# DotShine.net
KiCad netlist of a schematic drawn in EAGLE
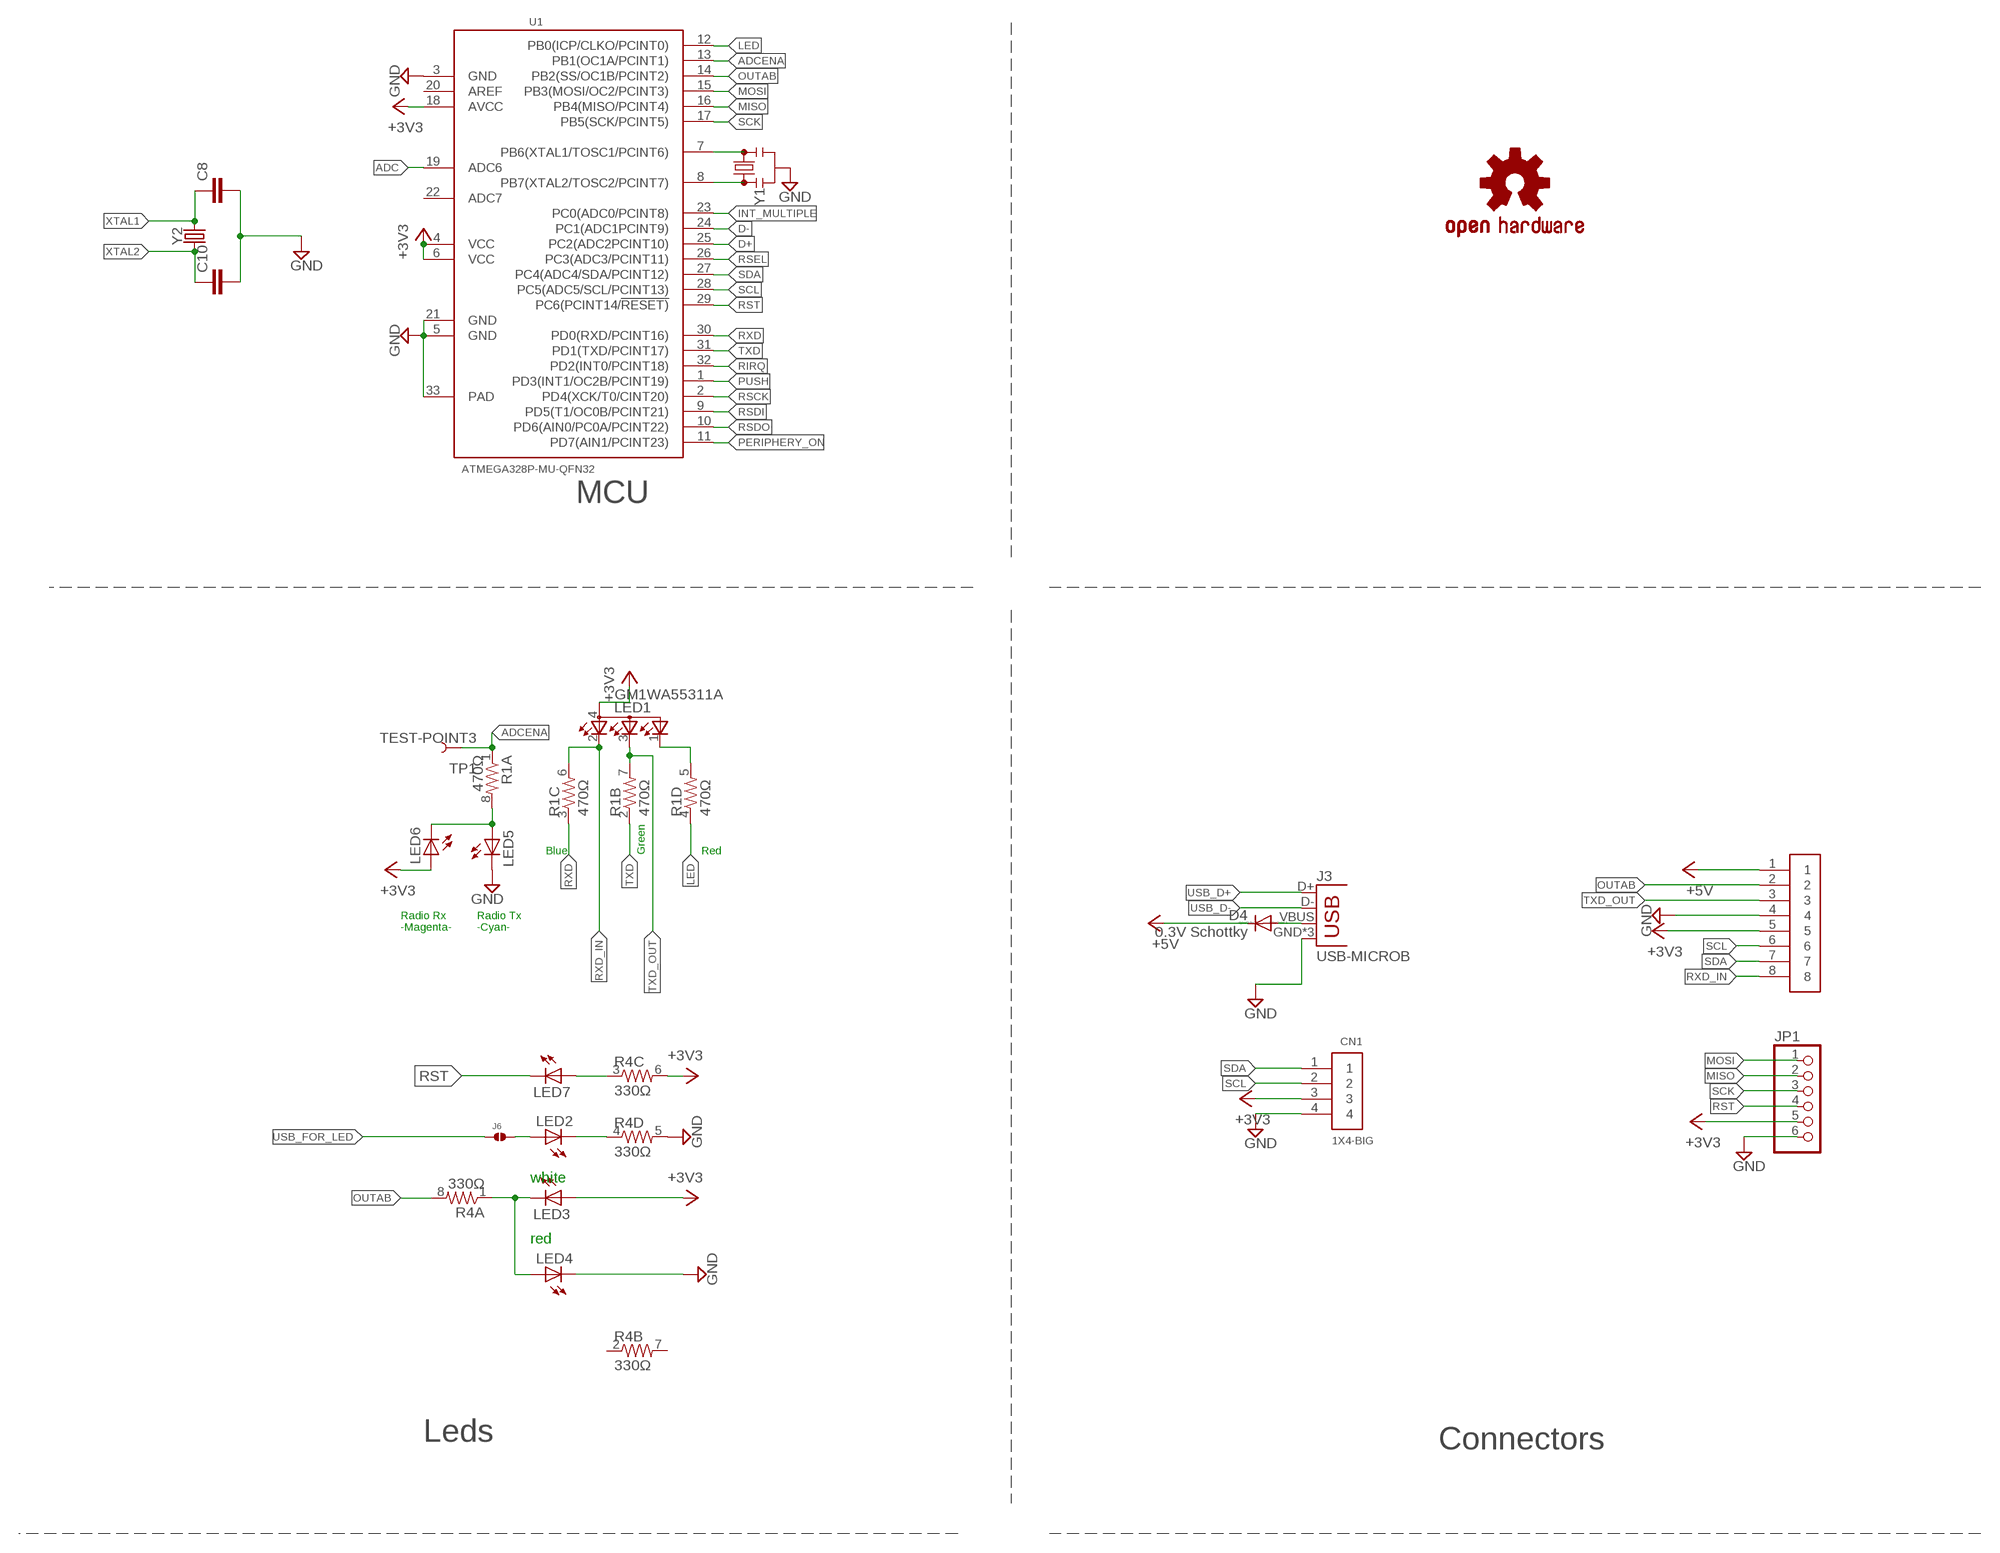
[diagram p0: schematic, sheet 1, part 1 of 3]
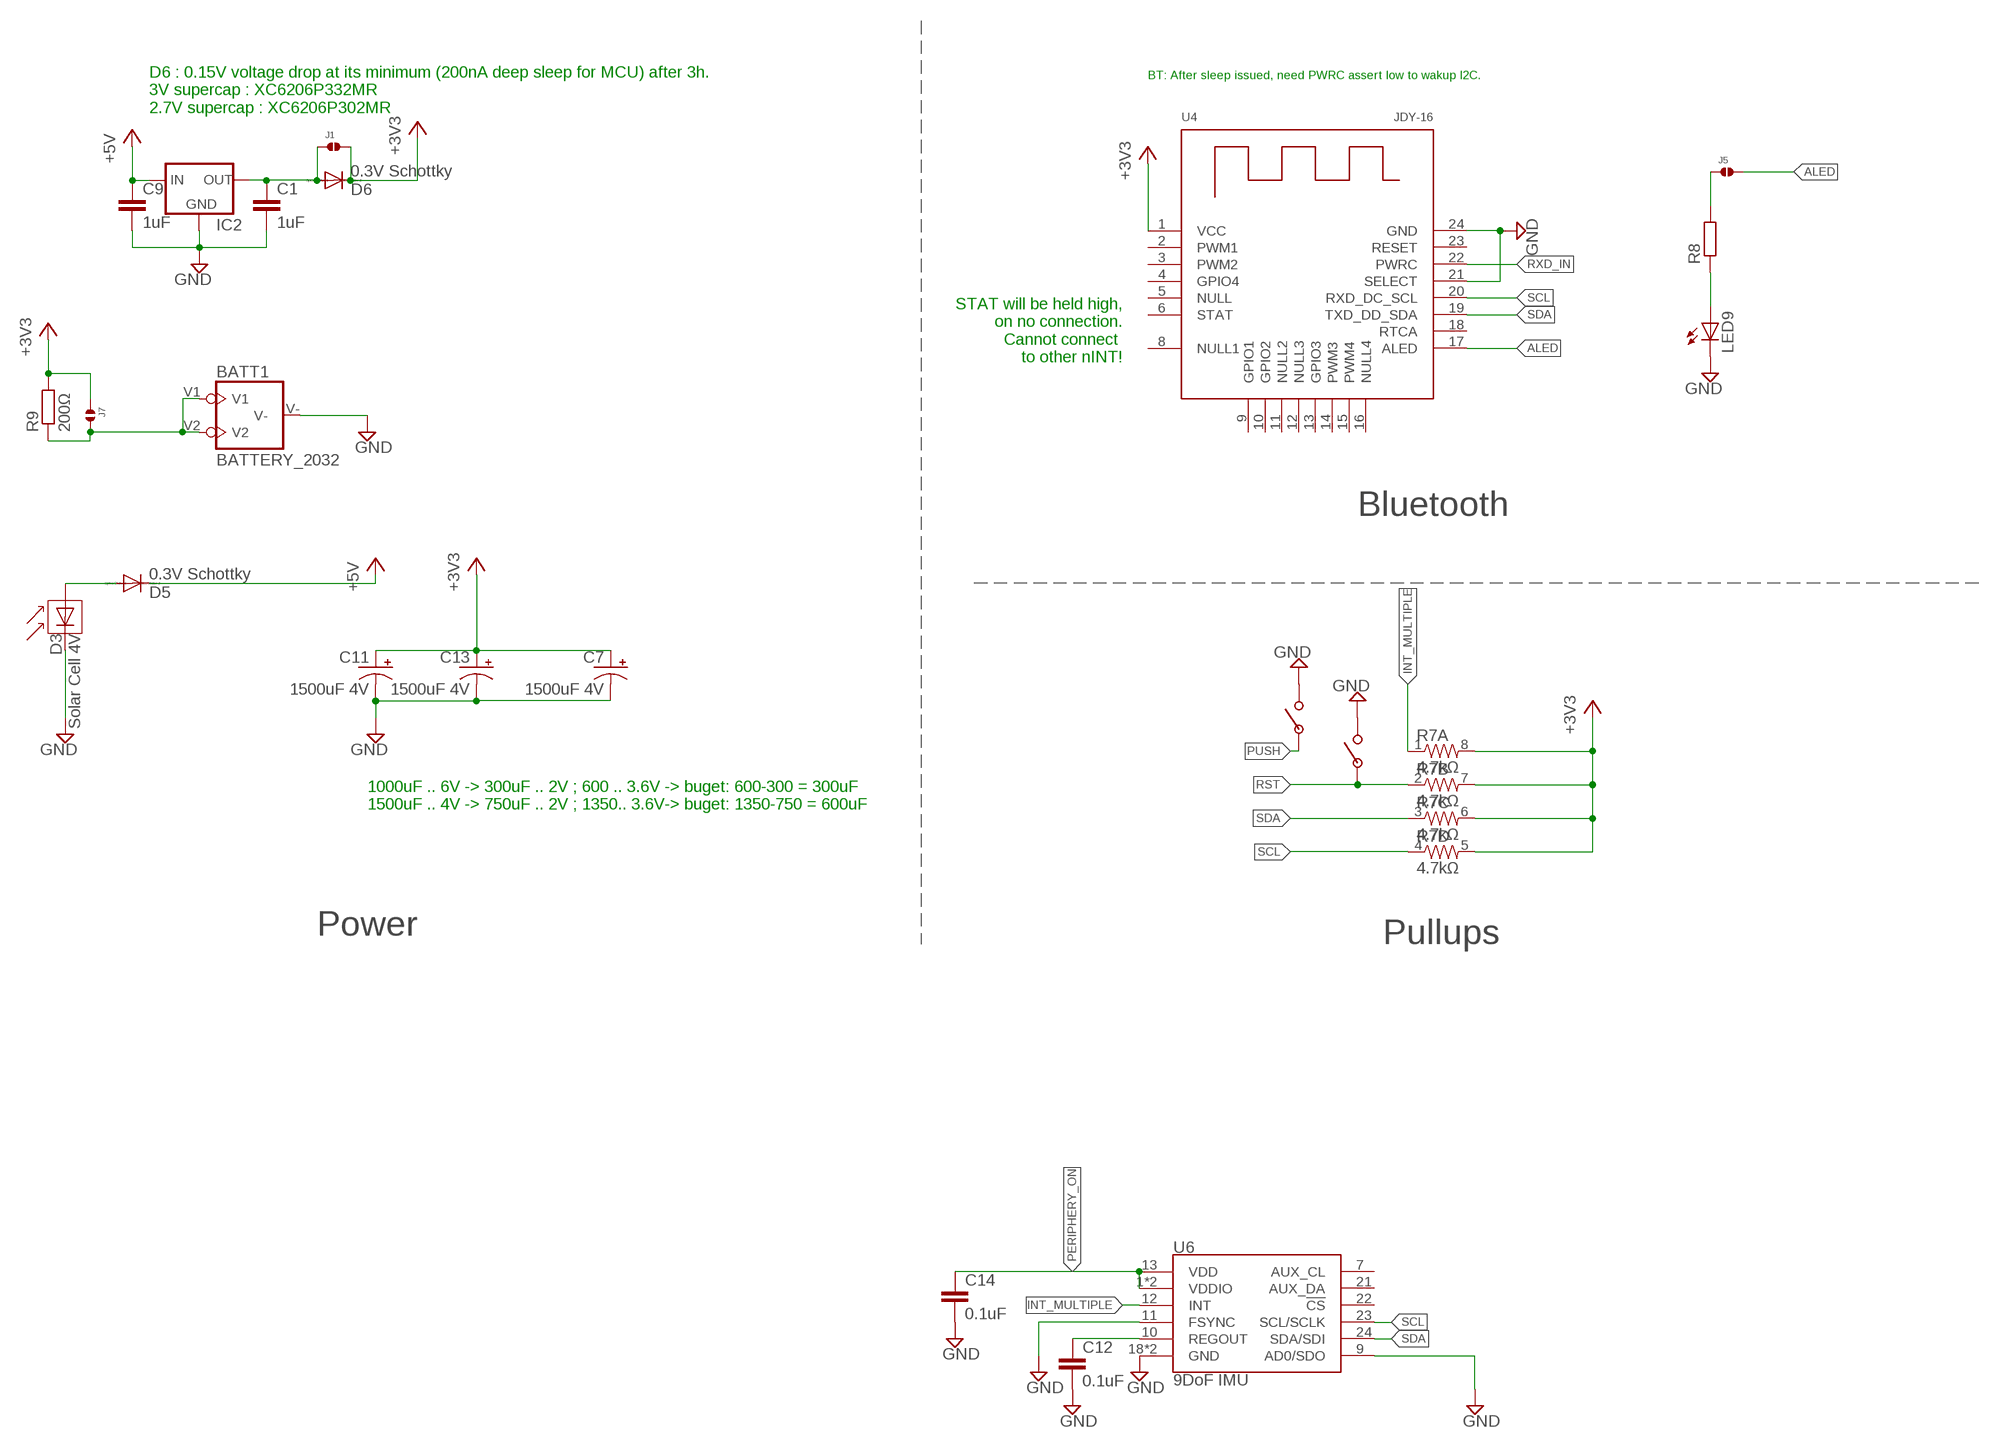
[diagram p1: schematic, sheet 1, part 2 of 3]
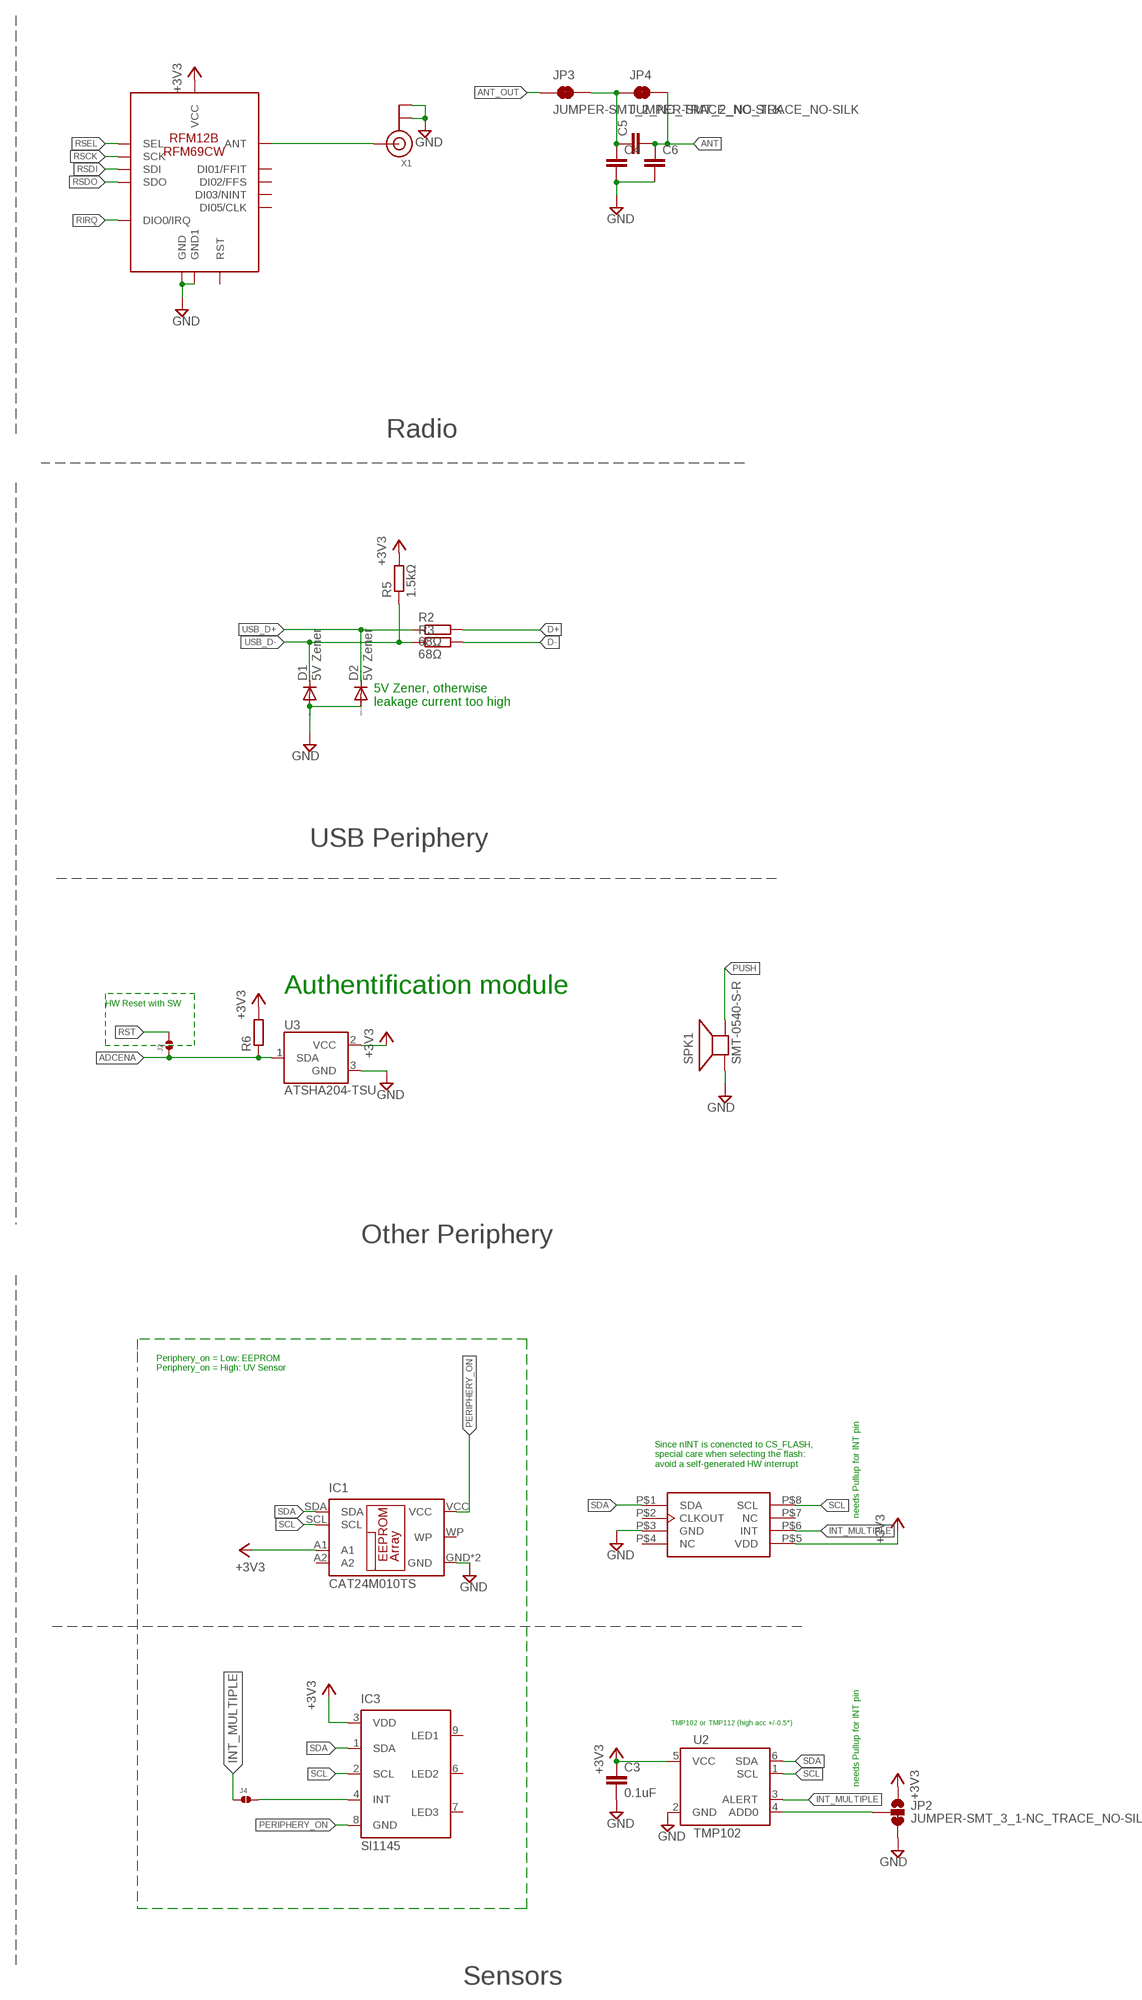
[diagram p2: schematic, sheet 1, part 3 of 3]

(export (version "E")
  (design (tool "Eeschema 10.0.6"))
  (components
    (comp (ref "BATT1")
      (value "BATTERY_2032")
      (footprint "eagle-import:BATT2032")
      (libsource (lib "eagle-import") (part "BATTERY_2032"))
    )
    (comp (ref "C1")
      (value "1uF")
      (footprint "eagle-import:C0603")
      (libsource (lib "eagle-import") (part "C-EUC0603"))
    )
    (comp (ref "C3")
      (value "0.1uF")
      (footprint "eagle-import:C0603")
      (libsource (lib "eagle-import") (part "resistor_C-EUC0603"))
    )
    (comp (ref "C4")
      (value "C-EUC0603")
      (footprint "eagle-import:C0603")
      (libsource (lib "eagle-import") (part "C-EUC0603"))
    )
    (comp (ref "C5")
      (value "C-EUC0603")
      (footprint "eagle-import:C0603")
      (libsource (lib "eagle-import") (part "C-EUC0603"))
    )
    (comp (ref "C6")
      (value "C-EUC0603")
      (footprint "eagle-import:C0603")
      (libsource (lib "eagle-import") (part "C-EUC0603"))
    )
    (comp (ref "C7")
      (value "1500uF 4V")
      (footprint "eagle-import:CT7343")
      (libsource (lib "eagle-import") (part "CPOL-USCT7343"))
    )
    (comp (ref "C8")
      (value "C-EUC0402")
      (footprint "eagle-import:C0402")
      (libsource (lib "eagle-import") (part "C-EUC0402"))
    )
    (comp (ref "C9")
      (value "1uF")
      (footprint "eagle-import:C0603")
      (libsource (lib "eagle-import") (part "C-EUC0603"))
    )
    (comp (ref "C10")
      (value "C-EUC0402")
      (footprint "eagle-import:C0402")
      (libsource (lib "eagle-import") (part "C-EUC0402"))
    )
    (comp (ref "C11")
      (value "1500uF 4V")
      (footprint "eagle-import:CT7343")
      (libsource (lib "eagle-import") (part "CPOL-USCT7343"))
    )
    (comp (ref "C12")
      (value "0.1uF")
      (footprint "eagle-import:C0603")
      (libsource (lib "eagle-import") (part "resistor_C-EUC0603"))
    )
    (comp (ref "C13")
      (value "1500uF 4V")
      (footprint "eagle-import:CT7343")
      (libsource (lib "eagle-import") (part "CPOL-USCT7343"))
    )
    (comp (ref "C14")
      (value "0.1uF")
      (footprint "eagle-import:C0603")
      (libsource (lib "eagle-import") (part "resistor_C-EUC0603"))
    )
    (comp (ref "CN1")
      (value "1X4-BIG")
      (footprint "eagle-import:1X04-BIG")
      (libsource (lib "eagle-import") (part "1X4-BIG"))
    )
    (comp (ref "D1")
      (value "5V Zener")
      (footprint "eagle-import:SOD523")
      (libsource (lib "eagle-import") (part "DIODE-SOD523"))
    )
    (comp (ref "D2")
      (value "5V Zener")
      (footprint "eagle-import:SOD523")
      (libsource (lib "eagle-import") (part "DIODE-SOD523"))
    )
    (comp (ref "D3")
      (value "Solar Cell 4V")
      (footprint "eagle-import:SOLARBIT-12X1")
      (libsource (lib "eagle-import") (part "SOLAR-IXYS-"))
    )
    (comp (ref "D4")
      (value "0.3V Schottky")
      (footprint "eagle-import:SOD523")
      (libsource (lib "eagle-import") (part "DIODE-SOD523"))
    )
    (comp (ref "D5")
      (value "0.3V Schottky")
      (footprint "eagle-import:SOD523")
      (libsource (lib "eagle-import") (part "DIODE-SOD523"))
    )
    (comp (ref "D6")
      (value "0.3V Schottky")
      (footprint "eagle-import:SOD523")
      (libsource (lib "eagle-import") (part "DIODE-SOD523"))
    )
    (comp (ref "IC1")
      (value "CAT24M010TS")
      (footprint "eagle-import:TSSOP8")
      (fields (field (name "MF") "On Semiconductor") (field (name "MPN") "24C00T-E/ST"))
      (libsource (lib "eagle-import") (part "CAT24M01TS0"))
    )
    (comp (ref "IC2")
      (value "MCP1700TT")
      (footprint "eagle-import:SOT-23")
      (libsource (lib "eagle-import") (part "MCP1700TT"))
    )
    (comp (ref "IC3")
      (value "SI1145")
      (footprint "eagle-import:QFN-10")
      (libsource (lib "eagle-import") (part "SI1145"))
    )
    (comp (ref "J1")
      (value "SOLDERJUMPER.2.MED")
      (footprint "eagle-import:2.MED")
      (libsource (lib "eagle-import") (part "SOLDERJUMPER.2.MED"))
    )
    (comp (ref "J2")
      (value "SOLDERJUMPER.2.MED")
      (footprint "eagle-import:2.MED")
      (libsource (lib "eagle-import") (part "SOLDERJUMPER.2.MED"))
    )
    (comp (ref "J3")
      (value "USB-MICROB")
      (footprint "eagle-import:USB-MICROB")
      (libsource (lib "eagle-import") (part "USB-MICROB"))
    )
    (comp (ref "J4")
      (value "SOLDERJUMPER.2.MED")
      (footprint "eagle-import:2.MED")
      (libsource (lib "eagle-import") (part "SOLDERJUMPER.2.MED"))
    )
    (comp (ref "J5")
      (value "SOLDERJUMPER.2.MED")
      (footprint "eagle-import:2.MED")
      (libsource (lib "eagle-import") (part "SOLDERJUMPER.2.MED"))
    )
    (comp (ref "J6")
      (value "SOLDERJUMPER.2.MED")
      (footprint "eagle-import:2.MED")
      (libsource (lib "eagle-import") (part "SOLDERJUMPER.2.MED"))
    )
    (comp (ref "J7")
      (value "SOLDERJUMPER.2.MED")
      (footprint "eagle-import:2.MED")
      (libsource (lib "eagle-import") (part "SOLDERJUMPER.2.MED"))
    )
    (comp (ref "JP1")
      (value "PINHD-1X6")
      (footprint "eagle-import:1X06")
      (libsource (lib "eagle-import") (part "PINHD-1X6"))
    )
    (comp (ref "JP2")
      (value "JUMPER-SMT_3_1-NC_TRACE_NO-SILK")
      (footprint "eagle-import:SMT-JUMPER_3_1-NC_TRACE_NO-SILK")
      (libsource (lib "eagle-import") (part "JUMPER-SMT_3_1-NC_TRACE_NO-SILK"))
    )
    (comp (ref "JP3")
      (value "JUMPER-SMT_2_NC_TRACE_NO-SILK")
      (footprint "eagle-import:SMT-JUMPER_2_NC_TRACE_NO-SILK")
      (libsource (lib "eagle-import") (part "JUMPER-SMT_2_NC_TRACE_NO-SILK"))
    )
    (comp (ref "JP4")
      (value "JUMPER-SMT_2_NC_TRACE_NO-SILK")
      (footprint "eagle-import:SMT-JUMPER_2_NC_TRACE_NO-SILK")
      (libsource (lib "eagle-import") (part "JUMPER-SMT_2_NC_TRACE_NO-SILK"))
    )
    (comp (ref "LED1")
      (value "GM1WA55311A")
      (footprint "eagle-import:GM1WA55311A")
      (libsource (lib "eagle-import") (part "GM1WA55311A"))
    )
    (comp (ref "LED2")
      (value "LED0603")
      (footprint "eagle-import:LED-0603")
      (libsource (lib "eagle-import") (part "LED0603"))
    )
    (comp (ref "LED3")
      (value "LED0603")
      (footprint "eagle-import:LED-0603")
      (libsource (lib "eagle-import") (part "LED0603"))
    )
    (comp (ref "LED4")
      (value "LED0603")
      (footprint "eagle-import:LED-0603")
      (libsource (lib "eagle-import") (part "LED0603"))
    )
    (comp (ref "LED5")
      (value "LED0603")
      (footprint "eagle-import:LED-0603")
      (libsource (lib "eagle-import") (part "LED0603"))
    )
    (comp (ref "LED6")
      (value "LED0603")
      (footprint "eagle-import:LED-0603")
      (libsource (lib "eagle-import") (part "LED0603"))
    )
    (comp (ref "LED7")
      (value "LED0603")
      (footprint "eagle-import:LED-0603")
      (libsource (lib "eagle-import") (part "LED0603"))
    )
    (comp (ref "LED9")
      (value "LED0603")
      (footprint "eagle-import:LED-0603")
      (libsource (lib "eagle-import") (part "LED0603"))
    )
    (comp (ref "LOGO1")
      (value "OSHW-LOGOS")
      (footprint "eagle-import:OSHW-LOGO-S")
      (libsource (lib "eagle-import") (part "OSHW-LOGOS"))
    )
    (comp (ref "R1")
      (value "470Ω")
      (footprint "eagle-import:0603-ARV")
      (libsource (lib "eagle-import") (part "RESISTOR-ARRAY0603-ARV"))
    )
    (comp (ref "R2")
      (value "68Ω")
      (footprint "eagle-import:R0603")
      (libsource (lib "eagle-import") (part "R-EU_R0603"))
    )
    (comp (ref "R3")
      (value "68Ω")
      (footprint "eagle-import:R0603")
      (libsource (lib "eagle-import") (part "R-EU_R0603"))
    )
    (comp (ref "R4")
      (value "330Ω")
      (footprint "eagle-import:0603-ARV")
      (libsource (lib "eagle-import") (part "RESISTOR-ARRAY0603-ARV"))
    )
    (comp (ref "R5")
      (value "1.5kΩ")
      (footprint "eagle-import:R0603")
      (libsource (lib "eagle-import") (part "R-EU_R0603"))
    )
    (comp (ref "R6")
      (value "R-EU_R0603")
      (footprint "eagle-import:R0603")
      (libsource (lib "eagle-import") (part "R-EU_R0603"))
    )
    (comp (ref "R7")
      (value "4.7kΩ")
      (footprint "eagle-import:0603-ARV")
      (libsource (lib "eagle-import") (part "RESISTOR-ARRAY0603-ARV"))
    )
    (comp (ref "R8")
      (value "R-EU_R0603")
      (footprint "eagle-import:R0603")
      (libsource (lib "eagle-import") (part "rcl_334_R-EU_R0603"))
    )
    (comp (ref "R9")
      (value "200Ω")
      (footprint "eagle-import:R0603")
      (libsource (lib "eagle-import") (part "R-EU_R0603"))
    )
    (comp (ref "SPK1")
      (value "SMT-0540-S-R")
      (footprint "eagle-import:SMT-0540-S-R")
      (libsource (lib "eagle-import") (part "SMT-0540-S-R"))
    )
    (comp (ref "TP1")
      (value "TEST-POINT3")
      (footprint "eagle-import:PAD.03X.03")
      (libsource (lib "eagle-import") (part "TEST-POINT3"))
    )
    (comp (ref "U$1")
      (value "RFM12B/69CW")
      (footprint "eagle-import:RFM12B_69CW")
      (libsource (lib "eagle-import") (part "RFM12B/69CW"))
    )
    (comp (ref "U$2")
      (value "PUSHBUTTON_4X2.5")
      (footprint "eagle-import:PUSHBUTTON_4X2.5")
      (libsource (lib "eagle-import") (part "PUSHBUTTON_4X2.5"))
    )
    (comp (ref "U$3")
      (value "PUSHBUTTON_4X2.5")
      (footprint "eagle-import:PUSHBUTTON_4X2.5")
      (libsource (lib "eagle-import") (part "PUSHBUTTON_4X2.5"))
    )
    (comp (ref "U$4")
      (value "JST-8")
      (footprint "eagle-import:S4B-ZR")
      (libsource (lib "eagle-import") (part "JST-8"))
    )
    (comp (ref "U1")
      (value "ATMEGA328P-MU-QFN32")
      (footprint "eagle-import:QFN32G-0.5-5X5MM")
      (fields (field (name "MPN") "ATMEGA328P-MU"))
      (libsource (lib "eagle-import") (part "MCU-ATMEGA328P-MU(QFN32)"))
    )
    (comp (ref "U2")
      (value "TMP102")
      (footprint "eagle-import:SOT563")
      (libsource (lib "eagle-import") (part "TMP102"))
    )
    (comp (ref "U3")
      (value "ATSHA204-TSU")
      (footprint "eagle-import:SOT23-3")
      (libsource (lib "eagle-import") (part "ATSHA204-TSU"))
    )
    (comp (ref "U4")
      (value "JDY-16")
      (footprint "eagle-import:JDY-16")
      (libsource (lib "eagle-import") (part "JDY-16"))
    )
    (comp (ref "U6")
      (value "9DoF IMU")
      (footprint "eagle-import:QFN24-3X3")
      (libsource (lib "eagle-import") (part "MPU-9250"))
    )
    (comp (ref "X1")
      (value "ANTENNA_U.FL")
      (footprint "eagle-import:U.FL")
      (libsource (lib "eagle-import") (part "ANTENNA_U.FL"))
    )
    (comp (ref "X2")
      (value "MC-RTC-RV-4162-C7-I2C")
      (footprint "eagle-import:MC-RTC-C7")
      (libsource (lib "eagle-import") (part "MC-RTC-RV-4162-C7-I2C"))
    )
    (comp (ref "Y1")
      (value "RESONATORSMD-3.2X1.3")
      (footprint "eagle-import:RESONATOR-SMD-3.2X1.3")
      (libsource (lib "eagle-import") (part "RESONATORSMD-3.2X1.3"))
    )
    (comp (ref "Y2")
      (value "CRYSTALSMD-3.2X1.5")
      (footprint "eagle-import:CRYSTAL-SMD-3.2X1.5MM")
      (libsource (lib "eagle-import") (part "CRYSTALSMD-3.2X1.5"))
    )
  )
  (nets
    (net (code "1") (name "+3V3") (class "Default")
      (node (ref "C11") (pin "+") (pinfunction "+_+") (pintype "passive"))
      (node (ref "C13") (pin "+") (pinfunction "+_+") (pintype "passive"))
      (node (ref "C3") (pin "1") (pinfunction "1_1") (pintype "passive"))
      (node (ref "C7") (pin "+") (pinfunction "+_+") (pintype "passive"))
      (node (ref "CN1") (pin "3") (pinfunction "3_3") (pintype "bidirectional"))
      (node (ref "D6") (pin "C") (pinfunction "C_C") (pintype "passive"))
      (node (ref "IC1") (pin "A1") (pinfunction "A1_A1") (pintype "bidirectional"))
      (node (ref "IC3") (pin "3") (pinfunction "VDD_3") (pintype "power_in"))
      (node (ref "J1") (pin "2") (pinfunction "2_2") (pintype "bidirectional"))
      (node (ref "J7") (pin "1") (pinfunction "1_1") (pintype "bidirectional"))
      (node (ref "JP1") (pin "5") (pinfunction "5_5") (pintype "passive"))
      (node (ref "JP2") (pin "1") (pinfunction "1_1") (pintype "passive"))
      (node (ref "LED1") (pin "4") (pinfunction "A_4") (pintype "passive"))
      (node (ref "LED3") (pin "A") (pinfunction "A_A") (pintype "passive"))
      (node (ref "LED6") (pin "A") (pinfunction "A_A") (pintype "passive"))
      (node (ref "R4") (pin "6") (pinfunction "2_6") (pintype "passive"))
      (node (ref "R5") (pin "2") (pinfunction "2_2") (pintype "passive"))
      (node (ref "R6") (pin "2") (pinfunction "2_2") (pintype "passive"))
      (node (ref "R7") (pin "5") (pinfunction "2_5") (pintype "passive"))
      (node (ref "R7") (pin "6") (pinfunction "2_6") (pintype "passive"))
      (node (ref "R7") (pin "7") (pinfunction "2_7") (pintype "passive"))
      (node (ref "R7") (pin "8") (pinfunction "2_8") (pintype "passive"))
      (node (ref "R9") (pin "2") (pinfunction "2_2") (pintype "passive"))
      (node (ref "U$1") (pin "VDD") (pinfunction "VCC_VDD") (pintype "power_in"))
      (node (ref "U$4") (pin "5") (pinfunction "5_5") (pintype "bidirectional"))
      (node (ref "U1") (pin "18") (pinfunction "AVCC_18") (pintype "bidirectional"))
      (node (ref "U1") (pin "4") (pinfunction "VCC_4") (pintype "bidirectional"))
      (node (ref "U1") (pin "6") (pinfunction "VCC_6") (pintype "bidirectional"))
      (node (ref "U2") (pin "5") (pinfunction "VCC_5") (pintype "bidirectional"))
      (node (ref "U3") (pin "2") (pinfunction "VCC_2") (pintype "bidirectional"))
      (node (ref "U4") (pin "1") (pinfunction "VCC_1") (pintype "bidirectional"))
      (node (ref "X2") (pin "P$5") (pinfunction "VDD_P$5") (pintype "power_in"))
    )
    (net (code "2") (name "+5V") (class "Default")
      (node (ref "C9") (pin "1") (pinfunction "1_1") (pintype "passive"))
      (node (ref "D4") (pin "C") (pinfunction "C_C") (pintype "passive"))
      (node (ref "D5") (pin "C") (pinfunction "C_C") (pintype "passive"))
      (node (ref "IC2") (pin "3") (pinfunction "IN_3") (pintype "input"))
      (node (ref "U$4") (pin "1") (pinfunction "1_1") (pintype "bidirectional"))
    )
    (net (code "3") (name "ADC") (class "Default")
      (node (ref "U1") (pin "19") (pinfunction "ADC6_19") (pintype "bidirectional"))
    )
    (net (code "4") (name "ADCENA") (class "Default")
      (node (ref "J2") (pin "1") (pinfunction "1_1") (pintype "bidirectional"))
      (node (ref "R1") (pin "1") (pinfunction "1_1") (pintype "passive"))
      (node (ref "R6") (pin "1") (pinfunction "1_1") (pintype "passive"))
      (node (ref "TP1") (pin "P$1") (pinfunction "1_P$1") (pintype "bidirectional"))
      (node (ref "U1") (pin "13") (pinfunction "PB1(OC1A/PCINT1)_13") (pintype "bidirectional"))
      (node (ref "U3") (pin "1") (pinfunction "SDA_1") (pintype "bidirectional"))
    )
    (net (code "5") (name "ALED") (class "Default")
      (node (ref "J5") (pin "2") (pinfunction "2_2") (pintype "bidirectional"))
      (node (ref "U4") (pin "17") (pinfunction "ALED_17") (pintype "bidirectional"))
    )
    (net (code "6") (name "ANT") (class "Default")
      (node (ref "C5") (pin "2") (pinfunction "2_2") (pintype "passive"))
      (node (ref "C6") (pin "1") (pinfunction "1_1") (pintype "passive"))
      (node (ref "JP4") (pin "2") (pinfunction "2_2") (pintype "passive"))
    )
    (net (code "7") (name "ANT_OUT") (class "Default")
      (node (ref "JP3") (pin "1") (pinfunction "1_1") (pintype "passive"))
      (node (ref "U$1") (pin "ANT") (pinfunction "ANT_ANT") (pintype "passive"))
      (node (ref "X1") (pin "3") (pinfunction "SIGNAL_3") (pintype "passive"))
    )
    (net (code "8") (name "D+") (class "Default")
      (node (ref "R2") (pin "2") (pinfunction "2_2") (pintype "passive"))
      (node (ref "U1") (pin "25") (pinfunction "PC2(ADC2PCINT10)_25") (pintype "bidirectional"))
    )
    (net (code "9") (name "D-") (class "Default")
      (node (ref "R3") (pin "2") (pinfunction "2_2") (pintype "passive"))
      (node (ref "U1") (pin "24") (pinfunction "PC1(ADC1PCINT9)_24") (pintype "bidirectional"))
    )
    (net (code "10") (name "GND") (class "Default")
      (node (ref "BATT1") (pin "V-") (pinfunction "V-_V-") (pintype "power_in"))
      (node (ref "C1") (pin "2") (pinfunction "2_2") (pintype "passive"))
      (node (ref "C10") (pin "2") (pinfunction "2_2") (pintype "passive"))
      (node (ref "C11") (pin "-") (pinfunction "-_-") (pintype "passive"))
      (node (ref "C12") (pin "2") (pinfunction "2_2") (pintype "passive"))
      (node (ref "C13") (pin "-") (pinfunction "-_-") (pintype "passive"))
      (node (ref "C14") (pin "2") (pinfunction "2_2") (pintype "passive"))
      (node (ref "C3") (pin "2") (pinfunction "2_2") (pintype "passive"))
      (node (ref "C4") (pin "2") (pinfunction "2_2") (pintype "passive"))
      (node (ref "C6") (pin "2") (pinfunction "2_2") (pintype "passive"))
      (node (ref "C7") (pin "-") (pinfunction "-_-") (pintype "passive"))
      (node (ref "C8") (pin "2") (pinfunction "2_2") (pintype "passive"))
      (node (ref "C9") (pin "2") (pinfunction "2_2") (pintype "passive"))
      (node (ref "CN1") (pin "4") (pinfunction "4_4") (pintype "bidirectional"))
      (node (ref "D1") (pin "A") (pinfunction "A_A") (pintype "passive"))
      (node (ref "D2") (pin "A") (pinfunction "A_A") (pintype "passive"))
      (node (ref "D3") (pin "-") (pinfunction "C_-") (pintype "passive"))
      (node (ref "IC1") (pin "GND") (pinfunction "GND_GND") (pintype "power_in"))
      (node (ref "IC1") (pin "NC") (pinfunction "GND_NC") (pintype "power_in"))
      (node (ref "IC2") (pin "1") (pinfunction "GND_1") (pintype "input"))
      (node (ref "J3") (pin "GND") (pinfunction "GND_GND") (pintype "bidirectional"))
      (node (ref "J3") (pin "MT1") (pinfunction "GND_MT1") (pintype "bidirectional"))
      (node (ref "J3") (pin "MT2") (pinfunction "GND_MT2") (pintype "bidirectional"))
      (node (ref "JP1") (pin "6") (pinfunction "6_6") (pintype "passive"))
      (node (ref "JP2") (pin "3") (pinfunction "3_3") (pintype "passive"))
      (node (ref "LED4") (pin "C") (pinfunction "C_C") (pintype "passive"))
      (node (ref "LED5") (pin "C") (pinfunction "C_C") (pintype "passive"))
      (node (ref "LED9") (pin "C") (pinfunction "C_C") (pintype "passive"))
      (node (ref "R4") (pin "5") (pinfunction "2_5") (pintype "passive"))
      (node (ref "SPK1") (pin "-") (pinfunction "+_-") (pintype "passive"))
      (node (ref "U$1") (pin "GND") (pinfunction "GND_GND") (pintype "power_in"))
      (node (ref "U$1") (pin "GND1") (pinfunction "GND1_GND1") (pintype "power_in"))
      (node (ref "U$2") (pin "P$2") (pinfunction "P$2_P$2") (pintype "bidirectional"))
      (node (ref "U$3") (pin "P$2") (pinfunction "P$2_P$2") (pintype "bidirectional"))
      (node (ref "U$4") (pin "4") (pinfunction "4_4") (pintype "bidirectional"))
      (node (ref "U1") (pin "21") (pinfunction "GND_21") (pintype "bidirectional"))
      (node (ref "U1") (pin "3") (pinfunction "GND_3") (pintype "bidirectional"))
      (node (ref "U1") (pin "33") (pinfunction "PAD_33") (pintype "bidirectional"))
      (node (ref "U1") (pin "5") (pinfunction "GND_5") (pintype "bidirectional"))
      (node (ref "U2") (pin "2") (pinfunction "GND_2") (pintype "bidirectional"))
      (node (ref "U3") (pin "3") (pinfunction "GND_3") (pintype "bidirectional"))
      (node (ref "U4") (pin "21") (pinfunction "SELECT_21") (pintype "bidirectional"))
      (node (ref "U4") (pin "24") (pinfunction "GND_24") (pintype "bidirectional"))
      (node (ref "U6") (pin "11") (pinfunction "FSYNC_11") (pintype "bidirectional"))
      (node (ref "U6") (pin "18") (pinfunction "GND_18") (pintype "bidirectional"))
      (node (ref "U6") (pin "20") (pinfunction "GND_20") (pintype "bidirectional"))
      (node (ref "U6") (pin "9") (pinfunction "AD0/SDO_9") (pintype "bidirectional"))
      (node (ref "X1") (pin "1") (pinfunction "GND_1") (pintype "passive"))
      (node (ref "X1") (pin "2") (pinfunction "GND_2") (pintype "passive"))
      (node (ref "X2") (pin "P$3") (pinfunction "GND_P$3") (pintype "power_in"))
      (node (ref "Y1") (pin "2") (pinfunction "2_2") (pintype "passive"))
    )
    (net (code "11") (name "INT_MULTIPLE") (class "Default")
      (node (ref "J4") (pin "1") (pinfunction "1_1") (pintype "bidirectional"))
      (node (ref "R7") (pin "1") (pinfunction "1_1") (pintype "passive"))
      (node (ref "U1") (pin "23") (pinfunction "PC0(ADC0/PCINT8)_23") (pintype "bidirectional"))
      (node (ref "U2") (pin "3") (pinfunction "ALERT_3") (pintype "bidirectional"))
      (node (ref "U6") (pin "12") (pinfunction "INT_12") (pintype "bidirectional"))
      (node (ref "X2") (pin "P$6") (pinfunction "INT_P$6") (pintype "bidirectional"))
    )
    (net (code "12") (name "LED") (class "Default")
      (node (ref "R1") (pin "4") (pinfunction "1_4") (pintype "passive"))
      (node (ref "U1") (pin "12") (pinfunction "PB0(ICP/CLKO/PCINT0)_12") (pintype "bidirectional"))
    )
    (net (code "13") (name "MISO") (class "Default")
      (node (ref "JP1") (pin "2") (pinfunction "2_2") (pintype "passive"))
      (node (ref "U1") (pin "16") (pinfunction "PB4(MISO/PCINT4)_16") (pintype "bidirectional"))
    )
    (net (code "14") (name "MOSI") (class "Default")
      (node (ref "JP1") (pin "1") (pinfunction "1_1") (pintype "passive"))
      (node (ref "U1") (pin "15") (pinfunction "PB3(MOSI/OC2/PCINT3)_15") (pintype "bidirectional"))
    )
    (net (code "15") (name "Net-(BATT1-PadV1)") (class "Default")
      (node (ref "BATT1") (pin "V1") (pinfunction "V1_V1") (pintype "power_in"))
      (node (ref "BATT1") (pin "V2") (pinfunction "V2_V2") (pintype "power_in"))
      (node (ref "J7") (pin "2") (pinfunction "2_2") (pintype "bidirectional"))
      (node (ref "R9") (pin "1") (pinfunction "1_1") (pintype "passive"))
    )
    (net (code "16") (name "Net-(C4-Pad1)") (class "Default")
      (node (ref "C4") (pin "1") (pinfunction "1_1") (pintype "passive"))
      (node (ref "C5") (pin "1") (pinfunction "1_1") (pintype "passive"))
      (node (ref "JP3") (pin "2") (pinfunction "2_2") (pintype "passive"))
      (node (ref "JP4") (pin "1") (pinfunction "1_1") (pintype "passive"))
    )
    (net (code "17") (name "Net-(D3-A)") (class "Default")
      (node (ref "D3") (pin "+") (pinfunction "A_+") (pintype "passive"))
      (node (ref "D5") (pin "A") (pinfunction "A_A") (pintype "passive"))
    )
    (net (code "18") (name "Net-(IC2-OUT)") (class "Default")
      (node (ref "C1") (pin "1") (pinfunction "1_1") (pintype "passive"))
      (node (ref "D6") (pin "A") (pinfunction "A_A") (pintype "passive"))
      (node (ref "IC2") (pin "2") (pinfunction "OUT_2") (pintype "passive"))
      (node (ref "J1") (pin "1") (pinfunction "1_1") (pintype "bidirectional"))
    )
    (net (code "19") (name "Net-(IC3-INT)") (class "Default")
      (node (ref "IC3") (pin "4") (pinfunction "INT_4") (pintype "open_collector"))
      (node (ref "J4") (pin "2") (pinfunction "2_2") (pintype "bidirectional"))
    )
    (net (code "20") (name "Net-(J5-Pad1)") (class "Default")
      (node (ref "J5") (pin "1") (pinfunction "1_1") (pintype "bidirectional"))
      (node (ref "R8") (pin "2") (pinfunction "2_2") (pintype "passive"))
    )
    (net (code "21") (name "Net-(J6-Pad2)") (class "Default")
      (node (ref "J6") (pin "2") (pinfunction "2_2") (pintype "bidirectional"))
      (node (ref "LED2") (pin "A") (pinfunction "A_A") (pintype "passive"))
    )
    (net (code "22") (name "Net-(LED1-CGREEN)") (class "Default")
      (node (ref "LED1") (pin "1") (pinfunction "CGREEN_1") (pintype "passive"))
      (node (ref "R1") (pin "5") (pinfunction "2_5") (pintype "passive"))
    )
    (net (code "23") (name "Net-(LED3-PadC)") (class "Default")
      (node (ref "LED3") (pin "C") (pinfunction "C_C") (pintype "passive"))
      (node (ref "LED4") (pin "A") (pinfunction "A_A") (pintype "passive"))
      (node (ref "R4") (pin "1") (pinfunction "1_1") (pintype "passive"))
    )
    (net (code "24") (name "Net-(LED9-PadA)") (class "Default")
      (node (ref "LED9") (pin "A") (pinfunction "A_A") (pintype "passive"))
      (node (ref "R8") (pin "1") (pinfunction "1_1") (pintype "passive"))
    )
    (net (code "25") (name "Net-(R1A-2)") (class "Default")
      (node (ref "LED5") (pin "A") (pinfunction "A_A") (pintype "passive"))
      (node (ref "LED6") (pin "C") (pinfunction "C_C") (pintype "passive"))
      (node (ref "R1") (pin "8") (pinfunction "2_8") (pintype "passive"))
    )
    (net (code "26") (name "Net-(R4C-1)") (class "Default")
      (node (ref "LED7") (pin "A") (pinfunction "A_A") (pintype "passive"))
      (node (ref "R4") (pin "3") (pinfunction "1_3") (pintype "passive"))
    )
    (net (code "27") (name "Net-(R4D-1)") (class "Default")
      (node (ref "LED2") (pin "C") (pinfunction "C_C") (pintype "passive"))
      (node (ref "R4") (pin "4") (pinfunction "1_4") (pintype "passive"))
    )
    (net (code "28") (name "Net-(U1-PB6(XTAL1{slash}TOSC1{slash}PCINT6))") (class "Default")
      (node (ref "U1") (pin "7") (pinfunction "PB6(XTAL1/TOSC1/PCINT6)_7") (pintype "bidirectional"))
      (node (ref "Y1") (pin "3") (pinfunction "3_3") (pintype "passive"))
    )
    (net (code "29") (name "Net-(U1-PB7(XTAL2{slash}TOSC2{slash}PCINT7))") (class "Default")
      (node (ref "U1") (pin "8") (pinfunction "PB7(XTAL2/TOSC2/PCINT7)_8") (pintype "bidirectional"))
      (node (ref "Y1") (pin "1") (pinfunction "1_1") (pintype "passive"))
    )
    (net (code "30") (name "Net-(U2-ADD0)") (class "Default")
      (node (ref "JP2") (pin "2") (pinfunction "2_2") (pintype "passive"))
      (node (ref "U2") (pin "4") (pinfunction "ADD0_4") (pintype "bidirectional"))
    )
    (net (code "31") (name "Net-(U6-REGOUT)") (class "Default")
      (node (ref "C12") (pin "1") (pinfunction "1_1") (pintype "passive"))
      (node (ref "U6") (pin "10") (pinfunction "REGOUT_10") (pintype "bidirectional"))
    )
    (net (code "32") (name "OUTAB") (class "Default")
      (node (ref "R4") (pin "8") (pinfunction "2_8") (pintype "passive"))
      (node (ref "U$4") (pin "2") (pinfunction "2_2") (pintype "bidirectional"))
      (node (ref "U1") (pin "14") (pinfunction "PB2(SS/OC1B/PCINT2)_14") (pintype "bidirectional"))
    )
    (net (code "33") (name "PERIPHERY_ON") (class "Default")
      (node (ref "C14") (pin "1") (pinfunction "1_1") (pintype "passive"))
      (node (ref "IC1") (pin "VCC") (pinfunction "VCC_VCC") (pintype "power_in"))
      (node (ref "IC3") (pin "8") (pinfunction "GND_8") (pintype "power_in"))
      (node (ref "U1") (pin "11") (pinfunction "PD7(AIN1/PCINT23)_11") (pintype "bidirectional"))
      (node (ref "U6") (pin "1") (pinfunction "VDDIO_1") (pintype "bidirectional"))
      (node (ref "U6") (pin "13") (pinfunction "VDD_13") (pintype "bidirectional"))
      (node (ref "U6") (pin "8") (pinfunction "VDDIO_8") (pintype "bidirectional"))
    )
    (net (code "34") (name "PUSH") (class "Default")
      (node (ref "SPK1") (pin "+") (pinfunction "-_+") (pintype "passive"))
      (node (ref "U$3") (pin "P$1") (pinfunction "P$1_P$1") (pintype "bidirectional"))
      (node (ref "U1") (pin "1") (pinfunction "PD3(INT1/OC2B/PCINT19)_1") (pintype "bidirectional"))
    )
    (net (code "35") (name "RIRQ") (class "Default")
      (node (ref "U$1") (pin "IRQ") (pinfunction "DIO0/IRQ_IRQ") (pintype "open_collector"))
      (node (ref "U1") (pin "32") (pinfunction "PD2(INT0/PCINT18)_32") (pintype "bidirectional"))
    )
    (net (code "36") (name "RSCK") (class "Default")
      (node (ref "U$1") (pin "SCK") (pinfunction "SCK_SCK") (pintype "input"))
      (node (ref "U1") (pin "2") (pinfunction "PD4(XCK/T0/CINT20)_2") (pintype "bidirectional"))
    )
    (net (code "37") (name "RSDI") (class "Default")
      (node (ref "U$1") (pin "SDI") (pinfunction "SDI_SDI") (pintype "input"))
      (node (ref "U1") (pin "9") (pinfunction "PD5(T1/OC0B/PCINT21)_9") (pintype "bidirectional"))
    )
    (net (code "38") (name "RSDO") (class "Default")
      (node (ref "U$1") (pin "SDO") (pinfunction "SDO_SDO") (pintype "output"))
      (node (ref "U1") (pin "10") (pinfunction "PD6(AIN0/PC0A/PCINT22)_10") (pintype "bidirectional"))
    )
    (net (code "39") (name "RSEL") (class "Default")
      (node (ref "U$1") (pin "SEL") (pinfunction "SEL_SEL") (pintype "input"))
      (node (ref "U1") (pin "26") (pinfunction "PC3(ADC3/PCINT11)_26") (pintype "bidirectional"))
    )
    (net (code "40") (name "RST") (class "Default")
      (node (ref "J2") (pin "2") (pinfunction "2_2") (pintype "bidirectional"))
      (node (ref "JP1") (pin "4") (pinfunction "4_4") (pintype "passive"))
      (node (ref "LED7") (pin "C") (pinfunction "C_C") (pintype "passive"))
      (node (ref "R7") (pin "2") (pinfunction "1_2") (pintype "passive"))
      (node (ref "U$2") (pin "P$1") (pinfunction "P$1_P$1") (pintype "bidirectional"))
      (node (ref "U1") (pin "29") (pinfunction "PC6(PCINT14/~{RESET})_29") (pintype "bidirectional"))
    )
    (net (code "41") (name "RXD") (class "Default")
      (node (ref "R1") (pin "3") (pinfunction "1_3") (pintype "passive"))
      (node (ref "U1") (pin "30") (pinfunction "PD0(RXD/PCINT16)_30") (pintype "bidirectional"))
    )
    (net (code "42") (name "RXD_IN") (class "Default")
      (node (ref "LED1") (pin "2") (pinfunction "CRED_2") (pintype "passive"))
      (node (ref "R1") (pin "6") (pinfunction "2_6") (pintype "passive"))
      (node (ref "U$4") (pin "8") (pinfunction "8_8") (pintype "bidirectional"))
      (node (ref "U4") (pin "22") (pinfunction "PWRC_22") (pintype "bidirectional"))
    )
    (net (code "43") (name "SCK") (class "Default")
      (node (ref "JP1") (pin "3") (pinfunction "3_3") (pintype "passive"))
      (node (ref "U1") (pin "17") (pinfunction "PB5(SCK/PCINT5)_17") (pintype "bidirectional"))
    )
    (net (code "44") (name "SCL") (class "Default")
      (node (ref "CN1") (pin "2") (pinfunction "2_2") (pintype "bidirectional"))
      (node (ref "IC1") (pin "SCL") (pinfunction "SCL_SCL") (pintype "input"))
      (node (ref "IC3") (pin "2") (pinfunction "SCL_2") (pintype "input"))
      (node (ref "R7") (pin "4") (pinfunction "1_4") (pintype "passive"))
      (node (ref "U$4") (pin "6") (pinfunction "6_6") (pintype "bidirectional"))
      (node (ref "U1") (pin "28") (pinfunction "PC5(ADC5/SCL/PCINT13)_28") (pintype "bidirectional"))
      (node (ref "U2") (pin "1") (pinfunction "SCL_1") (pintype "bidirectional"))
      (node (ref "U4") (pin "20") (pinfunction "RXD_DC_SCL_20") (pintype "bidirectional"))
      (node (ref "U6") (pin "23") (pinfunction "SCL/SCLK_23") (pintype "bidirectional"))
      (node (ref "X2") (pin "P$8") (pinfunction "SCL_P$8") (pintype "bidirectional"))
    )
    (net (code "45") (name "SDA") (class "Default")
      (node (ref "CN1") (pin "1") (pinfunction "1_1") (pintype "bidirectional"))
      (node (ref "IC1") (pin "SDA") (pinfunction "SDA_SDA") (pintype "bidirectional"))
      (node (ref "IC3") (pin "1") (pinfunction "SDA_1") (pintype "bidirectional"))
      (node (ref "R7") (pin "3") (pinfunction "1_3") (pintype "passive"))
      (node (ref "U$4") (pin "7") (pinfunction "7_7") (pintype "bidirectional"))
      (node (ref "U1") (pin "27") (pinfunction "PC4(ADC4/SDA/PCINT12)_27") (pintype "bidirectional"))
      (node (ref "U2") (pin "6") (pinfunction "SDA_6") (pintype "bidirectional"))
      (node (ref "U4") (pin "19") (pinfunction "TXD_DD_SDA_19") (pintype "bidirectional"))
      (node (ref "U6") (pin "24") (pinfunction "SDA/SDI_24") (pintype "bidirectional"))
      (node (ref "X2") (pin "P$1") (pinfunction "SDA_P$1") (pintype "bidirectional"))
    )
    (net (code "46") (name "TXD") (class "Default")
      (node (ref "R1") (pin "2") (pinfunction "1_2") (pintype "passive"))
      (node (ref "U1") (pin "31") (pinfunction "PD1(TXD/PCINT17)_31") (pintype "bidirectional"))
    )
    (net (code "47") (name "TXD_OUT") (class "Default")
      (node (ref "LED1") (pin "3") (pinfunction "CBLUE_3") (pintype "passive"))
      (node (ref "R1") (pin "7") (pinfunction "2_7") (pintype "passive"))
      (node (ref "U$4") (pin "3") (pinfunction "3_3") (pintype "bidirectional"))
    )
    (net (code "48") (name "USB_D+") (class "Default")
      (node (ref "D2") (pin "C") (pinfunction "C_C") (pintype "passive"))
      (node (ref "J3") (pin "D+") (pinfunction "D+_D+") (pintype "bidirectional"))
      (node (ref "R2") (pin "1") (pinfunction "1_1") (pintype "passive"))
    )
    (net (code "49") (name "USB_D-") (class "Default")
      (node (ref "D1") (pin "C") (pinfunction "C_C") (pintype "passive"))
      (node (ref "J3") (pin "D-") (pinfunction "D-_D-") (pintype "bidirectional"))
      (node (ref "R3") (pin "1") (pinfunction "1_1") (pintype "passive"))
      (node (ref "R5") (pin "1") (pinfunction "1_1") (pintype "passive"))
    )
    (net (code "50") (name "USB_FOR_LED") (class "Default")
      (node (ref "D4") (pin "A") (pinfunction "A_A") (pintype "passive"))
      (node (ref "J3") (pin "VBUS") (pinfunction "VBUS_VBUS") (pintype "bidirectional"))
      (node (ref "J6") (pin "1") (pinfunction "1_1") (pintype "bidirectional"))
    )
    (net (code "51") (name "XTAL1") (class "Default")
      (node (ref "C8") (pin "1") (pinfunction "1_1") (pintype "passive"))
      (node (ref "Y2") (pin "P$2") (pinfunction "2_P$2") (pintype "passive"))
    )
    (net (code "52") (name "XTAL2") (class "Default")
      (node (ref "C10") (pin "1") (pinfunction "1_1") (pintype "passive"))
      (node (ref "Y2") (pin "P$1") (pinfunction "1_P$1") (pintype "passive"))
    )
    (net (code "53") (name "unconnected-(IC1-PadA2)") (class "Default")
      (node (ref "IC1") (pin "A2") (pinfunction "A2_A2") (pintype "bidirectional"))
    )
    (net (code "54") (name "unconnected-(IC1-PadWP)") (class "Default")
      (node (ref "IC1") (pin "WP") (pinfunction "WP_WP") (pintype "bidirectional"))
    )
    (net (code "55") (name "unconnected-(IC3-LED1-Pad9)") (class "Default")
      (node (ref "IC3") (pin "9") (pinfunction "LED1_9") (pintype "output"))
    )
    (net (code "56") (name "unconnected-(IC3-LED2-Pad6)") (class "Default")
      (node (ref "IC3") (pin "6") (pinfunction "LED2_6") (pintype "output"))
    )
    (net (code "57") (name "unconnected-(IC3-LED3-Pad7)") (class "Default")
      (node (ref "IC3") (pin "7") (pinfunction "LED3_7") (pintype "output"))
    )
    (net (code "58") (name "unconnected-(R4B-1-Pad2)") (class "Default")
      (node (ref "R4") (pin "2") (pinfunction "1_2") (pintype "passive"))
    )
    (net (code "59") (name "unconnected-(R4B-2-Pad7)") (class "Default")
      (node (ref "R4") (pin "7") (pinfunction "2_7") (pintype "passive"))
    )
    (net (code "60") (name "unconnected-(U$1-DI01{slash}FFIT-PadFFIT)") (class "Default")
      (node (ref "U$1") (pin "FFIT") (pinfunction "DI01/FFIT_FFIT") (pintype "passive"))
    )
    (net (code "61") (name "unconnected-(U$1-DI02{slash}FFS-PadFFS)") (class "Default")
      (node (ref "U$1") (pin "FFS") (pinfunction "DI02/FFS_FFS") (pintype "bidirectional"))
    )
    (net (code "62") (name "unconnected-(U$1-DI03{slash}NINT-PadNINT)") (class "Default")
      (node (ref "U$1") (pin "NINT") (pinfunction "DI03/NINT_NINT") (pintype "passive"))
    )
    (net (code "63") (name "unconnected-(U$1-DI05{slash}CLK-PadCLK)") (class "Default")
      (node (ref "U$1") (pin "CLK") (pinfunction "DI05/CLK_CLK") (pintype "passive"))
    )
    (net (code "64") (name "unconnected-(U$1-PadRST)") (class "Default")
      (node (ref "U$1") (pin "RST") (pinfunction "RST_RST") (pintype "open_collector"))
    )
    (net (code "65") (name "unconnected-(U1-ADC7-Pad22)") (class "Default")
      (node (ref "U1") (pin "22") (pinfunction "ADC7_22") (pintype "bidirectional"))
    )
    (net (code "66") (name "unconnected-(U1-AREF-Pad20)") (class "Default")
      (node (ref "U1") (pin "20") (pinfunction "AREF_20") (pintype "bidirectional"))
    )
    (net (code "67") (name "unconnected-(U4-GPIO1-Pad9)") (class "Default")
      (node (ref "U4") (pin "9") (pinfunction "GPIO1_9") (pintype "bidirectional"))
    )
    (net (code "68") (name "unconnected-(U4-GPIO2-Pad10)") (class "Default")
      (node (ref "U4") (pin "10") (pinfunction "GPIO2_10") (pintype "bidirectional"))
    )
    (net (code "69") (name "unconnected-(U4-GPIO3-Pad13)") (class "Default")
      (node (ref "U4") (pin "13") (pinfunction "GPIO3_13") (pintype "bidirectional"))
    )
    (net (code "70") (name "unconnected-(U4-GPIO4-Pad4)") (class "Default")
      (node (ref "U4") (pin "4") (pinfunction "GPIO4_4") (pintype "bidirectional"))
    )
    (net (code "71") (name "unconnected-(U4-NULL-Pad5)") (class "Default")
      (node (ref "U4") (pin "5") (pinfunction "NULL_5") (pintype "bidirectional"))
    )
    (net (code "72") (name "unconnected-(U4-NULL1-Pad8)") (class "Default")
      (node (ref "U4") (pin "8") (pinfunction "NULL1_8") (pintype "bidirectional"))
    )
    (net (code "73") (name "unconnected-(U4-NULL2-Pad11)") (class "Default")
      (node (ref "U4") (pin "11") (pinfunction "NULL2_11") (pintype "bidirectional"))
    )
    (net (code "74") (name "unconnected-(U4-NULL3-Pad12)") (class "Default")
      (node (ref "U4") (pin "12") (pinfunction "NULL3_12") (pintype "bidirectional"))
    )
    (net (code "75") (name "unconnected-(U4-NULL4-Pad16)") (class "Default")
      (node (ref "U4") (pin "16") (pinfunction "NULL4_16") (pintype "bidirectional"))
    )
    (net (code "76") (name "unconnected-(U4-PWM1-Pad2)") (class "Default")
      (node (ref "U4") (pin "2") (pinfunction "PWM1_2") (pintype "bidirectional"))
    )
    (net (code "77") (name "unconnected-(U4-PWM2-Pad3)") (class "Default")
      (node (ref "U4") (pin "3") (pinfunction "PWM2_3") (pintype "bidirectional"))
    )
    (net (code "78") (name "unconnected-(U4-PWM3-Pad14)") (class "Default")
      (node (ref "U4") (pin "14") (pinfunction "PWM3_14") (pintype "bidirectional"))
    )
    (net (code "79") (name "unconnected-(U4-PWM4-Pad15)") (class "Default")
      (node (ref "U4") (pin "15") (pinfunction "PWM4_15") (pintype "bidirectional"))
    )
    (net (code "80") (name "unconnected-(U4-RESET-Pad23)") (class "Default")
      (node (ref "U4") (pin "23") (pinfunction "RESET_23") (pintype "bidirectional"))
    )
    (net (code "81") (name "unconnected-(U4-RTCA-Pad18)") (class "Default")
      (node (ref "U4") (pin "18") (pinfunction "RTCA_18") (pintype "bidirectional"))
    )
    (net (code "82") (name "unconnected-(U4-STAT-Pad6)") (class "Default")
      (node (ref "U4") (pin "6") (pinfunction "STAT_6") (pintype "bidirectional"))
    )
    (net (code "83") (name "unconnected-(U6-AUX_CL-Pad7)") (class "Default")
      (node (ref "U6") (pin "7") (pinfunction "AUX_CL_7") (pintype "bidirectional"))
    )
    (net (code "84") (name "unconnected-(U6-AUX_DA-Pad21)") (class "Default")
      (node (ref "U6") (pin "21") (pinfunction "AUX_DA_21") (pintype "bidirectional"))
    )
    (net (code "85") (name "unconnected-(U6-~{CS}-Pad22)") (class "Default")
      (node (ref "U6") (pin "22") (pinfunction "~{CS}_22") (pintype "bidirectional"))
    )
    (net (code "86") (name "unconnected-(X2-CLKOUT-PadP$2)") (class "Default")
      (node (ref "X2") (pin "P$2") (pinfunction "CLKOUT_P$2") (pintype "bidirectional"))
    )
    (net (code "87") (name "unconnected-(X2-NC-PadP$4)") (class "Default")
      (node (ref "X2") (pin "P$4") (pinfunction "NC_P$4") (pintype "no_connect"))
    )
    (net (code "88") (name "unconnected-(X2-NC-PadP$7)") (class "Default")
      (node (ref "X2") (pin "P$7") (pinfunction "NC_P$7") (pintype "no_connect"))
    )
  )
)
